# ground.net
KiCad netlist of a schematic drawn in Altium Designer
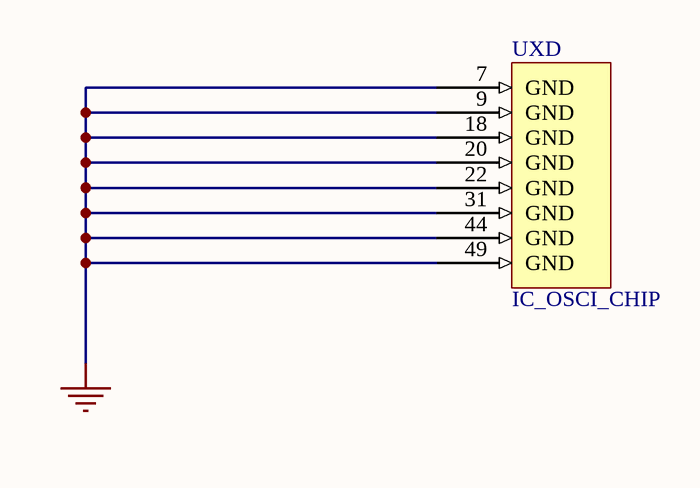
[diagram p0: ground.SchDoc]

(export (version "E")
  (design (tool "Eeschema 10.0.6"))
  (components
    (comp (ref "UX")
      (value "IC_OSCI_CHIP")
      (footprint "QFN-48-.4-6.0X6.0-LP")
      (description "EE290C Tapeout Class IC")
      (libsource (lib "schematic") (part "IC_OSCI_CHIP"))
    )
  )
  (nets
    (net (code "1") (name "GND") (class "Default")
      (node (ref "UX") (pin "18") (pinfunction "GND_18") (pintype "input"))
      (node (ref "UX") (pin "20") (pinfunction "GND_20") (pintype "input"))
      (node (ref "UX") (pin "22") (pinfunction "GND_22") (pintype "input"))
      (node (ref "UX") (pin "31") (pinfunction "GND_31") (pintype "input"))
      (node (ref "UX") (pin "44") (pinfunction "GND_44") (pintype "input"))
      (node (ref "UX") (pin "49") (pinfunction "GND_49") (pintype "input"))
      (node (ref "UX") (pin "7") (pinfunction "GND_7") (pintype "input"))
      (node (ref "UX") (pin "9") (pinfunction "GND_9") (pintype "input"))
    )
  )
)
